# Sheet1.net
KiCad netlist of a schematic drawn in Altium Designer
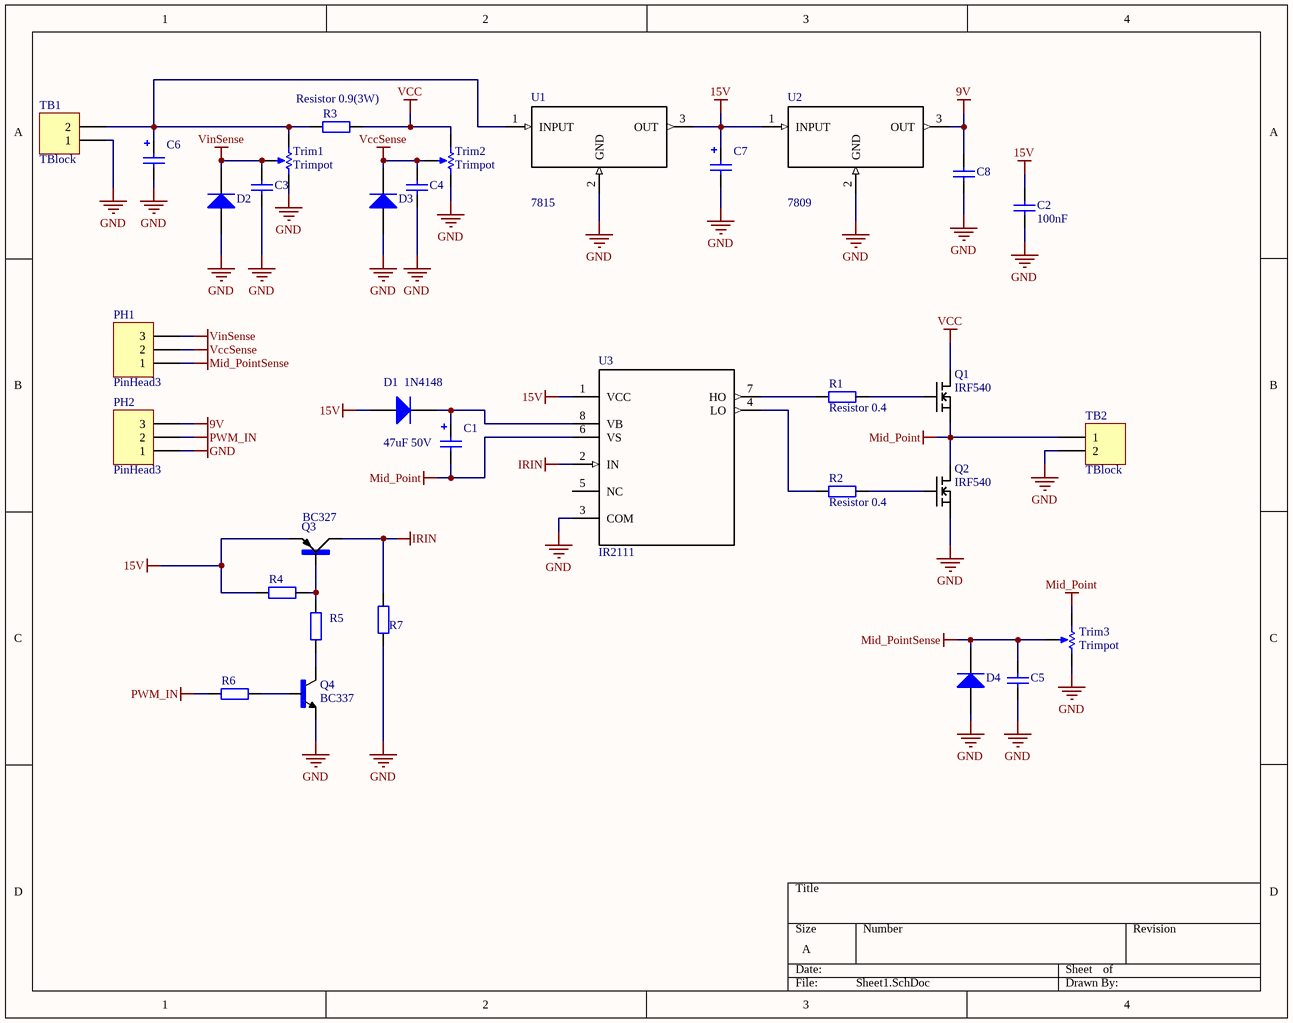
[diagram p0: Sheet1.SchDoc]

(export (version "E")
  (design (tool "Eeschema 10.0.6"))
  (components
    (comp (ref "C1")
      (value "47uF 50V")
      (footprint "Capacitor POL 2.2mm(100mil)")
      (libsource (lib "SPaivachlib1") (part "Capacitor 47uF 50V"))
    )
    (comp (ref "C2")
      (value "100nF")
      (footprint "Capacitor 100n (cor verniz)")
      (libsource (lib "SPaivachlib1") (part "Capacitor 100n 250V (Verniz)"))
    )
    (comp (ref "C3")
      (value "Capacitor 220nf 63V")
      (footprint "Capacitor NPOL 5mm(200mils)")
      (libsource (lib "SPaivachlib1") (part "Capacitor 220nf 63V"))
    )
    (comp (ref "C4")
      (value "Capacitor 220nf 63V")
      (footprint "Capacitor NPOL 5mm(200mils)")
      (libsource (lib "SPaivachlib1") (part "Capacitor 220nf 63V"))
    )
    (comp (ref "C5")
      (value "Capacitor 220nf 63V")
      (footprint "Capacitor NPOL 5mm(200mils)")
      (libsource (lib "SPaivachlib1") (part "Capacitor 220nf 63V"))
    )
    (comp (ref "C6")
      (value "Capacitor 1000uf 25V")
      (footprint "Capacitor 1000u 25V")
      (libsource (lib "SPaivachlib1") (part "Capacitor 1000uf 25V"))
    )
    (comp (ref "C7")
      (value "Capacitor 220uf 63V")
      (footprint "Capacitor 220uf 63V")
      (libsource (lib "SPaivachlib1") (part "Capacitor 220uf 63V"))
    )
    (comp (ref "C8")
      (value "Capacitor 220nf 63V")
      (footprint "Capacitor NPOL 5mm(200mils)")
      (libsource (lib "SPaivachlib1") (part "Capacitor 220nf 63V"))
    )
    (comp (ref "D1")
      (value "1N4148")
      (footprint "Diode 8.89mm(350mils)")
      (libsource (lib "SPaivachlib1") (part "Diode 1N4148"))
    )
    (comp (ref "D2")
      (value "Diode 1N4148")
      (footprint "Diode 8.89mm(350mils)")
      (libsource (lib "SPaivachlib1") (part "Diode 1N4148"))
    )
    (comp (ref "D3")
      (value "Diode 1N4148")
      (footprint "Diode 8.89mm(350mils)")
      (libsource (lib "SPaivachlib1") (part "Diode 1N4148"))
    )
    (comp (ref "D4")
      (value "Diode 1N4148")
      (footprint "Diode 8.89mm(350mils)")
      (libsource (lib "SPaivachlib1") (part "Diode 1N4148"))
    )
    (comp (ref "PH1")
      (value "PinHead3")
      (footprint "PINHEAD3")
      (libsource (lib "SPaivachlib1") (part "PinHead3"))
    )
    (comp (ref "PH2")
      (value "PinHead3")
      (footprint "PINHEAD3")
      (libsource (lib "SPaivachlib1") (part "PinHead3"))
    )
    (comp (ref "Q1") (value "IRF540") (footprint "IRF540") (libsource (lib "SPaivachlib1") (part "IRF540")))
    (comp (ref "Q2") (value "IRF540") (footprint "IRF540") (libsource (lib "SPaivachlib1") (part "IRF540")))
    (comp (ref "Q3") (value "BC327") (footprint "BC327") (libsource (lib "SPaivachlib1") (part "BC327")))
    (comp (ref "Q4") (value "BC337") (footprint "BC337") (libsource (lib "SPaivachlib1") (part "BC337")))
    (comp (ref "R1")
      (value "Resistor 0.4")
      (footprint "Resistor Axial 0.4")
      (libsource (lib "SPaivachlib1") (part "Resistor 0.4"))
    )
    (comp (ref "R2")
      (value "Resistor 0.4")
      (footprint "Resistor Axial 0.4")
      (libsource (lib "SPaivachlib1") (part "Resistor 0.4"))
    )
    (comp (ref "R3")
      (value "Resistor 0.9(3W)")
      (footprint "Resistor Axial 0.9(3W)")
      (libsource (lib "SPaivachlib1") (part "Resistor 0.9(3W)"))
    )
    (comp (ref "R4")
      (value "Resistor 0.4")
      (footprint "Resistor Axial 0.4")
      (libsource (lib "SPaivachlib1") (part "Resistor 0.4"))
    )
    (comp (ref "R5")
      (value "Resistor 0.4")
      (footprint "Resistor Axial 0.4")
      (libsource (lib "") (part "Resistor 0.4_1"))
    )
    (comp (ref "R6")
      (value "Resistor 0.4")
      (footprint "Resistor Axial 0.4")
      (libsource (lib "SPaivachlib1") (part "Resistor 0.4"))
    )
    (comp (ref "R7")
      (value "Resistor 0.4")
      (footprint "Resistor Axial 0.4")
      (libsource (lib "") (part "Resistor 0.4_1"))
    )
    (comp (ref "TB1") (value "TBlock") (footprint "TBlock") (libsource (lib "") (part "TBlock_1")))
    (comp (ref "TB2") (value "TBlock") (footprint "TBlock") (libsource (lib "SPaivachlib1") (part "TBlock")))
    (comp (ref "Trim1")
      (value "Trimpot")
      (footprint "TRIMPOT")
      (libsource (lib "SPaivachlib1") (part "Trimpot"))
    )
    (comp (ref "Trim2")
      (value "Trimpot")
      (footprint "TRIMPOT")
      (libsource (lib "SPaivachlib1") (part "Trimpot"))
    )
    (comp (ref "Trim3")
      (value "Trimpot")
      (footprint "TRIMPOT")
      (libsource (lib "SPaivachlib1") (part "Trimpot"))
    )
    (comp (ref "U1") (value "7815") (footprint "LM317/337") (libsource (lib "SPaivachlib1") (part "LM78XX")))
    (comp (ref "U2") (value "7809") (footprint "LM317/337") (libsource (lib "SPaivachlib1") (part "LM78XX")))
    (comp (ref "U3") (value "IR2111") (footprint "DIP8") (libsource (lib "SPaivachlib1") (part "IR2111")))
  )
  (nets
    (net (code "1") (name "9V") (class "Default")
      (node (ref "C8") (pin "2") (pinfunction "2_2") (pintype "passive"))
      (node (ref "PH2") (pin "3") (pinfunction "3_3") (pintype "passive"))
      (node (ref "U2") (pin "3") (pinfunction "OUT_3") (pintype "output"))
    )
    (net (code "2") (name "15V") (class "Default")
      (node (ref "C2") (pin "2") (pinfunction "2_2") (pintype "passive"))
      (node (ref "C7") (pin "2") (pinfunction "2_2") (pintype "passive"))
      (node (ref "D1") (pin "A") (pinfunction "A_A") (pintype "passive"))
      (node (ref "Q3") (pin "E") (pinfunction "E_E") (pintype "passive"))
      (node (ref "R4") (pin "1") (pinfunction "1_1") (pintype "passive"))
      (node (ref "U1") (pin "3") (pinfunction "OUT_3") (pintype "output"))
      (node (ref "U2") (pin "1") (pinfunction "INPUT_1") (pintype "input"))
      (node (ref "U3") (pin "1") (pinfunction "VCC_1") (pintype "power_in"))
    )
    (net (code "3") (name "GND") (class "Default")
      (node (ref "C2") (pin "1") (pinfunction "1_1") (pintype "passive"))
      (node (ref "C3") (pin "1") (pinfunction "1_1") (pintype "passive"))
      (node (ref "C4") (pin "1") (pinfunction "1_1") (pintype "passive"))
      (node (ref "C5") (pin "1") (pinfunction "1_1") (pintype "passive"))
      (node (ref "C6") (pin "1") (pinfunction "1_1") (pintype "passive"))
      (node (ref "C7") (pin "1") (pinfunction "1_1") (pintype "passive"))
      (node (ref "C8") (pin "1") (pinfunction "1_1") (pintype "passive"))
      (node (ref "D2") (pin "A") (pinfunction "A_A") (pintype "passive"))
      (node (ref "D3") (pin "A") (pinfunction "A_A") (pintype "passive"))
      (node (ref "D4") (pin "A") (pinfunction "A_A") (pintype "passive"))
      (node (ref "PH2") (pin "1") (pinfunction "1_1") (pintype "passive"))
      (node (ref "Q2") (pin "3") (pinfunction "S_3") (pintype "passive"))
      (node (ref "Q4") (pin "1") (pinfunction "E_1") (pintype "passive"))
      (node (ref "R7") (pin "1") (pinfunction "1_1") (pintype "passive"))
      (node (ref "TB1") (pin "1") (pinfunction "1_1") (pintype "passive"))
      (node (ref "TB2") (pin "2") (pinfunction "2_2") (pintype "passive"))
      (node (ref "Trim1") (pin "3") (pinfunction "BOT_3") (pintype "passive"))
      (node (ref "Trim2") (pin "3") (pinfunction "BOT_3") (pintype "passive"))
      (node (ref "Trim3") (pin "3") (pinfunction "BOT_3") (pintype "passive"))
      (node (ref "U1") (pin "2") (pinfunction "GND_2") (pintype "input"))
      (node (ref "U2") (pin "2") (pinfunction "GND_2") (pintype "input"))
      (node (ref "U3") (pin "3") (pinfunction "COM_3") (pintype "passive"))
    )
    (net (code "4") (name "IRIN") (class "Default")
      (node (ref "Q3") (pin "C") (pinfunction "C_C") (pintype "passive"))
      (node (ref "R7") (pin "2") (pinfunction "2_2") (pintype "passive"))
      (node (ref "U3") (pin "2") (pinfunction "IN_2") (pintype "input"))
    )
    (net (code "5") (name "Mid_Point") (class "Default")
      (node (ref "C1") (pin "1") (pinfunction "1_1") (pintype "passive"))
      (node (ref "Q1") (pin "3") (pinfunction "S_3") (pintype "passive"))
      (node (ref "Q2") (pin "2") (pinfunction "D_2") (pintype "passive"))
      (node (ref "TB2") (pin "1") (pinfunction "1_1") (pintype "passive"))
      (node (ref "Trim3") (pin "1") (pinfunction "TOP_1") (pintype "passive"))
      (node (ref "U3") (pin "6") (pinfunction "VS_6") (pintype "power_in"))
    )
    (net (code "6") (name "Mid_PointSense") (class "Default")
      (node (ref "C5") (pin "2") (pinfunction "2_2") (pintype "passive"))
      (node (ref "D4") (pin "K") (pinfunction "K_K") (pintype "passive"))
      (node (ref "PH1") (pin "1") (pinfunction "1_1") (pintype "passive"))
      (node (ref "Trim3") (pin "2") (pinfunction "TAP_2") (pintype "passive"))
    )
    (net (code "7") (name "Net-(Q1-G)") (class "Default")
      (node (ref "Q1") (pin "1") (pinfunction "G_1") (pintype "passive"))
      (node (ref "R1") (pin "2") (pinfunction "2_2") (pintype "passive"))
    )
    (net (code "8") (name "Net-(Q2-G)") (class "Default")
      (node (ref "Q2") (pin "1") (pinfunction "G_1") (pintype "passive"))
      (node (ref "R2") (pin "2") (pinfunction "2_2") (pintype "passive"))
    )
    (net (code "9") (name "Net-(Q3-PadB)") (class "Default")
      (node (ref "Q3") (pin "B") (pinfunction "B_B") (pintype "passive"))
      (node (ref "R4") (pin "2") (pinfunction "2_2") (pintype "passive"))
      (node (ref "R5") (pin "2") (pinfunction "2_2") (pintype "passive"))
    )
    (net (code "10") (name "Net-(Q4-B)") (class "Default")
      (node (ref "Q4") (pin "2") (pinfunction "B_2") (pintype "passive"))
      (node (ref "R6") (pin "2") (pinfunction "2_2") (pintype "passive"))
    )
    (net (code "11") (name "Net-(Q4-C)") (class "Default")
      (node (ref "Q4") (pin "3") (pinfunction "C_3") (pintype "passive"))
      (node (ref "R5") (pin "1") (pinfunction "1_1") (pintype "passive"))
    )
    (net (code "12") (name "Net-(Trim1-TOP)") (class "Default")
      (node (ref "C6") (pin "2") (pinfunction "2_2") (pintype "passive"))
      (node (ref "R3") (pin "1") (pinfunction "1_1") (pintype "passive"))
      (node (ref "TB1") (pin "2") (pinfunction "2_2") (pintype "passive"))
      (node (ref "Trim1") (pin "1") (pinfunction "TOP_1") (pintype "passive"))
      (node (ref "U1") (pin "1") (pinfunction "INPUT_1") (pintype "input"))
    )
    (net (code "13") (name "Net-(U3-HO)") (class "Default")
      (node (ref "R1") (pin "1") (pinfunction "1_1") (pintype "passive"))
      (node (ref "U3") (pin "7") (pinfunction "HO_7") (pintype "output"))
    )
    (net (code "14") (name "Net-(U3-LO)") (class "Default")
      (node (ref "R2") (pin "1") (pinfunction "1_1") (pintype "passive"))
      (node (ref "U3") (pin "4") (pinfunction "LO_4") (pintype "output"))
    )
    (net (code "15") (name "Net-(U3-VB)") (class "Default")
      (node (ref "C1") (pin "2") (pinfunction "2_2") (pintype "passive"))
      (node (ref "D1") (pin "K") (pinfunction "K_K") (pintype "passive"))
      (node (ref "U3") (pin "8") (pinfunction "VB_8") (pintype "power_in"))
    )
    (net (code "16") (name "PWM_IN") (class "Default")
      (node (ref "PH2") (pin "2") (pinfunction "2_2") (pintype "passive"))
      (node (ref "R6") (pin "1") (pinfunction "1_1") (pintype "passive"))
    )
    (net (code "17") (name "VCC") (class "Default")
      (node (ref "Q1") (pin "2") (pinfunction "D_2") (pintype "passive"))
      (node (ref "R3") (pin "2") (pinfunction "2_2") (pintype "passive"))
      (node (ref "Trim2") (pin "1") (pinfunction "TOP_1") (pintype "passive"))
    )
    (net (code "18") (name "VccSense") (class "Default")
      (node (ref "C4") (pin "2") (pinfunction "2_2") (pintype "passive"))
      (node (ref "D3") (pin "K") (pinfunction "K_K") (pintype "passive"))
      (node (ref "PH1") (pin "2") (pinfunction "2_2") (pintype "passive"))
      (node (ref "Trim2") (pin "2") (pinfunction "TAP_2") (pintype "passive"))
    )
    (net (code "19") (name "VinSense") (class "Default")
      (node (ref "C3") (pin "2") (pinfunction "2_2") (pintype "passive"))
      (node (ref "D2") (pin "K") (pinfunction "K_K") (pintype "passive"))
      (node (ref "PH1") (pin "3") (pinfunction "3_3") (pintype "passive"))
      (node (ref "Trim1") (pin "2") (pinfunction "TAP_2") (pintype "passive"))
    )
    (net (code "20") (name "unconnected-(U3-NC-Pad5)") (class "Default")
      (node (ref "U3") (pin "5") (pinfunction "NC_5") (pintype "passive"))
    )
  )
)
